# Schematic_v2.net
KiCad netlist of a schematic drawn in EAGLE
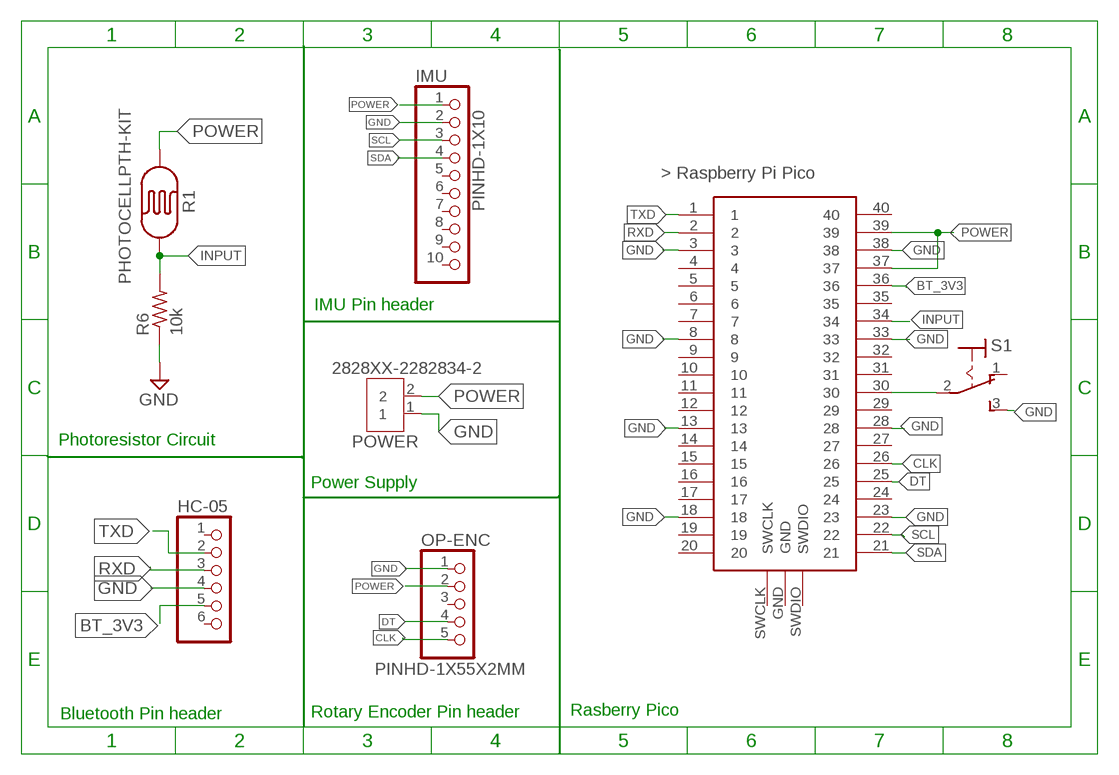
[diagram p0: schematic, sheet 1]

(export (version "E")
  (design (tool "Eeschema 10.0.6"))
  (components
    (comp (ref "HC-05")
      (value "PINHD-1X6")
      (footprint "eagle-import:1X06")
      (libsource (lib "eagle-import") (part "PINHD-1X6"))
    )
    (comp (ref "IMU")
      (value "PINHD-1X10")
      (footprint "eagle-import:1X10-BIG")
      (libsource (lib "eagle-import") (part "PINHD-1X10"))
    )
    (comp (ref "OP-ENC")
      (value "PINHD-1X55X2MM")
      (footprint "eagle-import:1_05X2MM")
      (libsource (lib "eagle-import") (part "PINHD-1X55X2MM"))
    )
    (comp (ref "PICO")
      (value "RASPBERRY-PI-PICO_TH")
      (footprint "eagle-import:FT_RASPBERRY-PI-PICO_TH")
      (libsource (lib "eagle-import") (part "RASPBERRY-PI-PICO_TH"))
    )
    (comp (ref "POWER")
      (value "2828XX-2282834-2")
      (footprint "eagle-import:TERMBLK_254-2N")
      (libsource (lib "eagle-import") (part "2828XX-2282834-2"))
    )
    (comp (ref "R1")
      (value "PHOTOCELLPTH-KIT")
      (footprint "eagle-import:PHOTOCELL-KIT")
      (libsource (lib "eagle-import") (part "PHOTOCELLPTH-KIT"))
    )
    (comp (ref "R6")
      (value "10k")
      (footprint "eagle-import:0207_10")
      (libsource (lib "eagle-import") (part "RESISTOR_1/4W_0207/10"))
    )
    (comp (ref "S1")
      (value "320-916")
      (footprint "eagle-import:320-916")
      (libsource (lib "eagle-import") (part "320-916"))
    )
  )
  (nets
    (net (code "1") (name "BT_3V3") (class "Default")
      (node (ref "HC-05") (pin "5") (pinfunction "5_5") (pintype "passive"))
      (node (ref "PICO") (pin "36") (pinfunction "36_36") (pintype "bidirectional"))
    )
    (net (code "2") (name "CLK") (class "Default")
      (node (ref "OP-ENC") (pin "5") (pinfunction "5_5") (pintype "passive"))
      (node (ref "PICO") (pin "26") (pinfunction "26_26") (pintype "bidirectional"))
    )
    (net (code "3") (name "DT") (class "Default")
      (node (ref "OP-ENC") (pin "4") (pinfunction "4_4") (pintype "passive"))
      (node (ref "PICO") (pin "25") (pinfunction "25_25") (pintype "bidirectional"))
    )
    (net (code "4") (name "GND") (class "Default")
      (node (ref "HC-05") (pin "4") (pinfunction "4_4") (pintype "passive"))
      (node (ref "IMU") (pin "2") (pinfunction "2_2") (pintype "passive"))
      (node (ref "OP-ENC") (pin "1") (pinfunction "1_1") (pintype "passive"))
      (node (ref "PICO") (pin "13") (pinfunction "13_13") (pintype "bidirectional"))
      (node (ref "PICO") (pin "18") (pinfunction "18_18") (pintype "bidirectional"))
      (node (ref "PICO") (pin "23") (pinfunction "23_23") (pintype "bidirectional"))
      (node (ref "PICO") (pin "28") (pinfunction "28_28") (pintype "bidirectional"))
      (node (ref "PICO") (pin "3") (pinfunction "3_3") (pintype "bidirectional"))
      (node (ref "PICO") (pin "33") (pinfunction "33_33") (pintype "bidirectional"))
      (node (ref "PICO") (pin "38") (pinfunction "38_38") (pintype "bidirectional"))
      (node (ref "PICO") (pin "8") (pinfunction "8_8") (pintype "bidirectional"))
      (node (ref "POWER") (pin "1") (pinfunction "1_1") (pintype "bidirectional"))
      (node (ref "R6") (pin "1") (pinfunction "1_1") (pintype "passive"))
      (node (ref "S1") (pin "3") (pinfunction "S_3") (pintype "passive"))
    )
    (net (code "5") (name "INPUT") (class "Default")
      (node (ref "PICO") (pin "34") (pinfunction "34_34") (pintype "bidirectional"))
      (node (ref "R1") (pin "1") (pinfunction "P$1_1") (pintype "bidirectional"))
      (node (ref "R6") (pin "2") (pinfunction "2_2") (pintype "passive"))
    )
    (net (code "6") (name "Net-(S1-P)") (class "Default")
      (node (ref "PICO") (pin "30") (pinfunction "30_30") (pintype "bidirectional"))
      (node (ref "S1") (pin "2") (pinfunction "P_2") (pintype "passive"))
    )
    (net (code "7") (name "POWER") (class "Default")
      (node (ref "IMU") (pin "1") (pinfunction "1_1") (pintype "passive"))
      (node (ref "OP-ENC") (pin "2") (pinfunction "2_2") (pintype "passive"))
      (node (ref "PICO") (pin "37") (pinfunction "37_37") (pintype "bidirectional"))
      (node (ref "PICO") (pin "39") (pinfunction "39_39") (pintype "bidirectional"))
      (node (ref "POWER") (pin "2") (pinfunction "2_2") (pintype "bidirectional"))
      (node (ref "R1") (pin "2") (pinfunction "P$2_2") (pintype "bidirectional"))
    )
    (net (code "8") (name "RXD") (class "Default")
      (node (ref "HC-05") (pin "3") (pinfunction "3_3") (pintype "passive"))
      (node (ref "PICO") (pin "2") (pinfunction "2_2") (pintype "bidirectional"))
    )
    (net (code "9") (name "SCL") (class "Default")
      (node (ref "IMU") (pin "3") (pinfunction "3_3") (pintype "passive"))
      (node (ref "PICO") (pin "22") (pinfunction "22_22") (pintype "bidirectional"))
    )
    (net (code "10") (name "SDA") (class "Default")
      (node (ref "IMU") (pin "4") (pinfunction "4_4") (pintype "passive"))
      (node (ref "PICO") (pin "21") (pinfunction "21_21") (pintype "bidirectional"))
    )
    (net (code "11") (name "TXD") (class "Default")
      (node (ref "HC-05") (pin "2") (pinfunction "2_2") (pintype "passive"))
      (node (ref "PICO") (pin "1") (pinfunction "1_1") (pintype "bidirectional"))
    )
    (net (code "12") (name "unconnected-(HC-05-Pad1)") (class "Default")
      (node (ref "HC-05") (pin "1") (pinfunction "1_1") (pintype "passive"))
    )
    (net (code "13") (name "unconnected-(HC-05-Pad6)") (class "Default")
      (node (ref "HC-05") (pin "6") (pinfunction "6_6") (pintype "passive"))
    )
    (net (code "14") (name "unconnected-(IMU-Pad5)") (class "Default")
      (node (ref "IMU") (pin "5") (pinfunction "5_5") (pintype "passive"))
    )
    (net (code "15") (name "unconnected-(IMU-Pad6)") (class "Default")
      (node (ref "IMU") (pin "6") (pinfunction "6_6") (pintype "passive"))
    )
    (net (code "16") (name "unconnected-(IMU-Pad7)") (class "Default")
      (node (ref "IMU") (pin "7") (pinfunction "7_7") (pintype "passive"))
    )
    (net (code "17") (name "unconnected-(IMU-Pad8)") (class "Default")
      (node (ref "IMU") (pin "8") (pinfunction "8_8") (pintype "passive"))
    )
    (net (code "18") (name "unconnected-(IMU-Pad9)") (class "Default")
      (node (ref "IMU") (pin "9") (pinfunction "9_9") (pintype "passive"))
    )
    (net (code "19") (name "unconnected-(IMU-Pad10)") (class "Default")
      (node (ref "IMU") (pin "10") (pinfunction "10_10") (pintype "passive"))
    )
    (net (code "20") (name "unconnected-(OP-ENC-Pad3)") (class "Default")
      (node (ref "OP-ENC") (pin "3") (pinfunction "3_3") (pintype "passive"))
    )
    (net (code "21") (name "unconnected-(PICO-Pad4)") (class "Default")
      (node (ref "PICO") (pin "4") (pinfunction "4_4") (pintype "bidirectional"))
    )
    (net (code "22") (name "unconnected-(PICO-Pad5)") (class "Default")
      (node (ref "PICO") (pin "5") (pinfunction "5_5") (pintype "bidirectional"))
    )
    (net (code "23") (name "unconnected-(PICO-Pad6)") (class "Default")
      (node (ref "PICO") (pin "6") (pinfunction "6_6") (pintype "bidirectional"))
    )
    (net (code "24") (name "unconnected-(PICO-Pad7)") (class "Default")
      (node (ref "PICO") (pin "7") (pinfunction "7_7") (pintype "bidirectional"))
    )
    (net (code "25") (name "unconnected-(PICO-Pad9)") (class "Default")
      (node (ref "PICO") (pin "9") (pinfunction "9_9") (pintype "bidirectional"))
    )
    (net (code "26") (name "unconnected-(PICO-Pad10)") (class "Default")
      (node (ref "PICO") (pin "10") (pinfunction "10_10") (pintype "bidirectional"))
    )
    (net (code "27") (name "unconnected-(PICO-Pad11)") (class "Default")
      (node (ref "PICO") (pin "11") (pinfunction "11_11") (pintype "bidirectional"))
    )
    (net (code "28") (name "unconnected-(PICO-Pad12)") (class "Default")
      (node (ref "PICO") (pin "12") (pinfunction "12_12") (pintype "bidirectional"))
    )
    (net (code "29") (name "unconnected-(PICO-Pad14)") (class "Default")
      (node (ref "PICO") (pin "14") (pinfunction "14_14") (pintype "bidirectional"))
    )
    (net (code "30") (name "unconnected-(PICO-Pad15)") (class "Default")
      (node (ref "PICO") (pin "15") (pinfunction "15_15") (pintype "bidirectional"))
    )
    (net (code "31") (name "unconnected-(PICO-Pad16)") (class "Default")
      (node (ref "PICO") (pin "16") (pinfunction "16_16") (pintype "bidirectional"))
    )
    (net (code "32") (name "unconnected-(PICO-Pad17)") (class "Default")
      (node (ref "PICO") (pin "17") (pinfunction "17_17") (pintype "bidirectional"))
    )
    (net (code "33") (name "unconnected-(PICO-Pad19)") (class "Default")
      (node (ref "PICO") (pin "19") (pinfunction "19_19") (pintype "bidirectional"))
    )
    (net (code "34") (name "unconnected-(PICO-Pad20)") (class "Default")
      (node (ref "PICO") (pin "20") (pinfunction "20_20") (pintype "bidirectional"))
    )
    (net (code "35") (name "unconnected-(PICO-Pad24)") (class "Default")
      (node (ref "PICO") (pin "24") (pinfunction "24_24") (pintype "bidirectional"))
    )
    (net (code "36") (name "unconnected-(PICO-Pad27)") (class "Default")
      (node (ref "PICO") (pin "27") (pinfunction "27_27") (pintype "bidirectional"))
    )
    (net (code "37") (name "unconnected-(PICO-Pad29)") (class "Default")
      (node (ref "PICO") (pin "29") (pinfunction "29_29") (pintype "bidirectional"))
    )
    (net (code "38") (name "unconnected-(PICO-Pad31)") (class "Default")
      (node (ref "PICO") (pin "31") (pinfunction "31_31") (pintype "bidirectional"))
    )
    (net (code "39") (name "unconnected-(PICO-Pad32)") (class "Default")
      (node (ref "PICO") (pin "32") (pinfunction "32_32") (pintype "bidirectional"))
    )
    (net (code "40") (name "unconnected-(PICO-Pad35)") (class "Default")
      (node (ref "PICO") (pin "35") (pinfunction "35_35") (pintype "bidirectional"))
    )
    (net (code "41") (name "unconnected-(PICO-Pad40)") (class "Default")
      (node (ref "PICO") (pin "40") (pinfunction "40_40") (pintype "bidirectional"))
    )
    (net (code "42") (name "unconnected-(PICO-PadGND)") (class "Default")
      (node (ref "PICO") (pin "GND") (pinfunction "GND_GND") (pintype "bidirectional"))
    )
    (net (code "43") (name "unconnected-(PICO-PadSWCLK)") (class "Default")
      (node (ref "PICO") (pin "SWCLK") (pinfunction "SWCLK_SWCLK") (pintype "bidirectional"))
    )
    (net (code "44") (name "unconnected-(PICO-PadSWDIO)") (class "Default")
      (node (ref "PICO") (pin "SWDIO") (pinfunction "SWDIO_SWDIO") (pintype "bidirectional"))
    )
    (net (code "45") (name "unconnected-(S1-O-Pad1)") (class "Default")
      (node (ref "S1") (pin "1") (pinfunction "O_1") (pintype "passive"))
    )
  )
)
